# SW6208_C_LED__188.net
KiCad netlist of a schematic drawn in Altium Designer
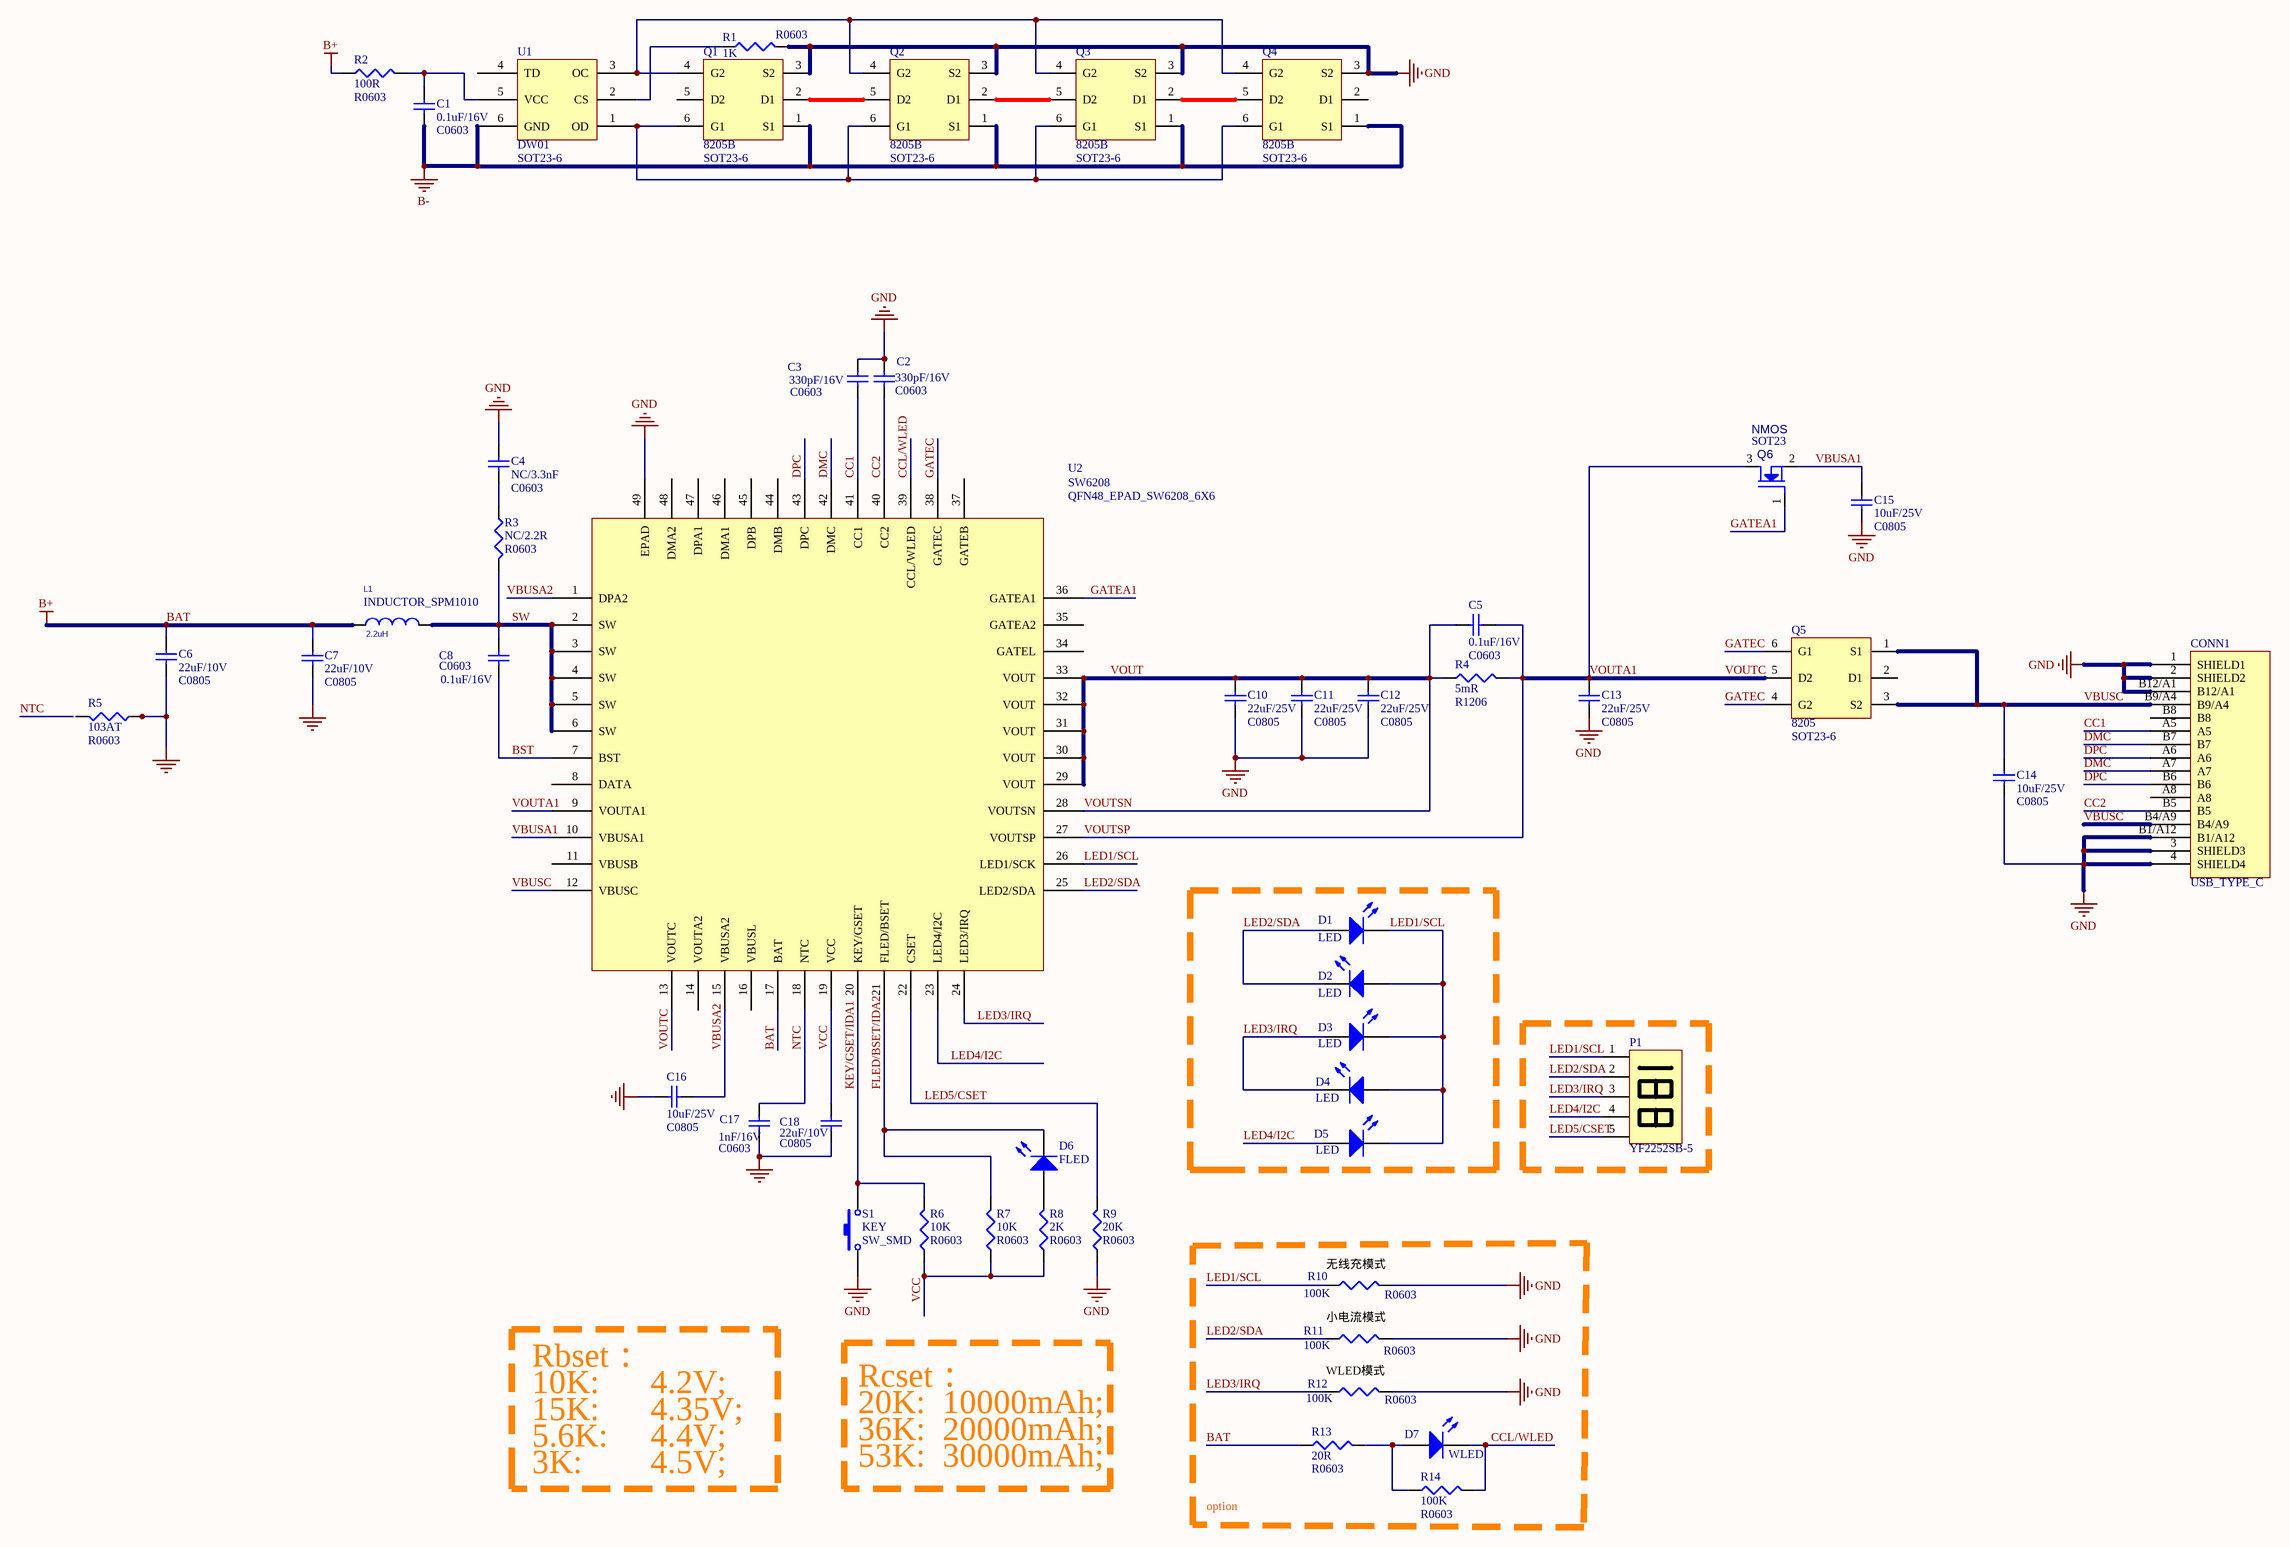
[diagram p0: SW6208+C+LED_普通188数码管.SchDoc]

(export (version "E")
  (design (tool "Eeschema 10.0.6"))
  (components
    (comp (ref "C1")
      (value "0.1uF/16V")
      (footprint "C0603")
      (description "Capacitor")
      (fields (field (name "PUBLISHER") "Altium Limited"))
      (libsource (lib "参考设计器件原理图更新") (part "CAP0603"))
    )
    (comp (ref "C2")
      (value "330pF/16V")
      (footprint "C0603")
      (description "Capacitor")
      (fields (field (name "PUBLISHER") "Altium Limited"))
      (libsource (lib "参考设计器件原理图更新") (part "CAP0603"))
    )
    (comp (ref "C3")
      (value "330pF/16V")
      (footprint "C0603")
      (description "Capacitor")
      (fields (field (name "PUBLISHER") "Altium Limited"))
      (libsource (lib "参考设计器件原理图更新") (part "CAP0603"))
    )
    (comp (ref "C4")
      (value "NC/3.3nF")
      (footprint "C0603")
      (description "Capacitor")
      (fields (field (name "PUBLISHER") "Altium Limited"))
      (libsource (lib "参考设计器件原理图更新") (part "CAP0603"))
    )
    (comp (ref "C5")
      (value "0.1uF/16V")
      (footprint "C0603")
      (description "Capacitor")
      (fields (field (name "PUBLISHER") "Altium Limited"))
      (libsource (lib "参考设计器件原理图更新") (part "CAP0603"))
    )
    (comp (ref "C6")
      (value "22uF/10V")
      (footprint "C0805")
      (description "Capacitor")
      (fields (field (name "PUBLISHER") "Altium Limited"))
      (libsource (lib "参考设计器件原理图更新") (part "CAP0805"))
    )
    (comp (ref "C7")
      (value "22uF/10V")
      (footprint "C0805")
      (description "Capacitor")
      (fields (field (name "PUBLISHER") "Altium Limited"))
      (libsource (lib "参考设计器件原理图更新") (part "CAP0805"))
    )
    (comp (ref "C8")
      (value "0.1uF/16V")
      (footprint "C0603")
      (description "Capacitor")
      (fields (field (name "PUBLISHER") "Altium Limited"))
      (libsource (lib "参考设计器件原理图更新") (part "CAP0603"))
    )
    (comp (ref "C10")
      (value "22uF/25V")
      (footprint "C0805")
      (description "Capacitor")
      (fields (field (name "PUBLISHER") "Altium Limited"))
      (libsource (lib "参考设计器件原理图更新") (part "CAP0805"))
    )
    (comp (ref "C11")
      (value "22uF/25V")
      (footprint "C0805")
      (description "Capacitor")
      (fields (field (name "PUBLISHER") "Altium Limited"))
      (libsource (lib "参考设计器件原理图更新") (part "CAP0805"))
    )
    (comp (ref "C12")
      (value "22uF/25V")
      (footprint "C0805")
      (description "Capacitor")
      (fields (field (name "PUBLISHER") "Altium Limited"))
      (libsource (lib "参考设计器件原理图更新") (part "CAP0805"))
    )
    (comp (ref "C13")
      (value "22uF/25V")
      (footprint "C0805")
      (description "Capacitor")
      (fields (field (name "PUBLISHER") "Altium Limited"))
      (libsource (lib "参考设计器件原理图更新") (part "CAP0805"))
    )
    (comp (ref "C14")
      (value "10uF/25V")
      (footprint "C0805")
      (description "Capacitor")
      (fields (field (name "PUBLISHER") "Altium Limited"))
      (libsource (lib "参考设计器件原理图更新") (part "CAP0805"))
    )
    (comp (ref "C15")
      (value "10uF/25V")
      (footprint "C0805")
      (description "Capacitor")
      (fields (field (name "PUBLISHER") "Altium Limited"))
      (libsource (lib "参考设计器件原理图更新") (part "CAP0805"))
    )
    (comp (ref "C16")
      (value "10uF/25V")
      (footprint "C0805")
      (description "Capacitor")
      (fields (field (name "PUBLISHER") "Altium Limited"))
      (libsource (lib "参考设计器件原理图更新") (part "CAP0805"))
    )
    (comp (ref "C17")
      (value "1nF/16V")
      (footprint "C0603")
      (description "Capacitor")
      (fields (field (name "PUBLISHER") "Altium Limited"))
      (libsource (lib "参考设计器件原理图更新") (part "CAP0603"))
    )
    (comp (ref "C18")
      (value "22uF/10V")
      (footprint "C0805")
      (description "Capacitor")
      (fields (field (name "PUBLISHER") "Altium Limited"))
      (libsource (lib "参考设计器件原理图更新") (part "CAP0805"))
    )
    (comp (ref "CONN1")
      (value "USB_TYPE_C")
      (footprint "LOUISAD:USB_TYPE_C")
      (libsource (lib "参考设计器件原理图更新") (part "USB_TYPE_C"))
    )
    (comp (ref "D1")
      (value "LED")
      (footprint "LED0603")
      (fields (field (name "PUBLISHER") "Altium Limited"))
      (libsource (lib "参考设计器件原理图更新") (part "LED_0603"))
    )
    (comp (ref "D2")
      (value "LED")
      (footprint "LED0603")
      (fields (field (name "PUBLISHER") "Altium Limited"))
      (libsource (lib "参考设计器件原理图更新") (part "LED_0603"))
    )
    (comp (ref "D3")
      (value "LED")
      (footprint "LED0603")
      (fields (field (name "PUBLISHER") "Altium Limited"))
      (libsource (lib "参考设计器件原理图更新") (part "LED_0603"))
    )
    (comp (ref "D4")
      (value "LED")
      (footprint "LED0603")
      (fields (field (name "PUBLISHER") "Altium Limited"))
      (libsource (lib "参考设计器件原理图更新") (part "LED_0603"))
    )
    (comp (ref "D5")
      (value "LED")
      (footprint "LED0603")
      (fields (field (name "PUBLISHER") "Altium Limited"))
      (libsource (lib "参考设计器件原理图更新") (part "LED_0603"))
    )
    (comp (ref "D6")
      (value "FLED")
      (footprint "LED0603")
      (description "LED")
      (fields (field (name "PUBLISHER") "Altium Limited"))
      (libsource (lib "参考设计器件原理图更新") (part "LED_0603"))
    )
    (comp (ref "D7")
      (value "WLED")
      (footprint "LED_5MM")
      (fields (field (name "PUBLISHER") "Altium Limited"))
      (libsource (lib "参考设计器件原理图更新") (part "WLED"))
    )
    (comp (ref "L1")
      (value "2.2uH")
      (footprint "INDUCTOR_SPM1010")
      (description "INDUCTOR")
      (libsource (lib "参考设计器件原理图更新") (part "INDUCTOR_SPM1010"))
    )
    (comp (ref "P1")
      (value "YF2252SB-5")
      (footprint "LED_Display_5")
      (description "188_LED_Display")
      (libsource (lib "参考设计器件原理图更新") (part "LED_Display_5"))
    )
    (comp (ref "Q1")
      (value "8205B")
      (footprint "SOT23-6")
      (description "NMOS")
      (fields (field (name "FOOTPRINF") "SOT23-6"))
      (libsource (lib "") (part "8205_1"))
    )
    (comp (ref "Q2")
      (value "8205B")
      (footprint "SOT23-6")
      (description "NMOS")
      (fields (field (name "FOOTPRINF") "SOT23-6"))
      (libsource (lib "") (part "8205_1"))
    )
    (comp (ref "Q3")
      (value "8205B")
      (footprint "SOT23-6")
      (description "NMOS")
      (fields (field (name "FOOTPRINF") "SOT23-6"))
      (libsource (lib "") (part "8205_1"))
    )
    (comp (ref "Q4")
      (value "8205B")
      (footprint "SOT23-6")
      (description "NMOS")
      (fields (field (name "FOOTPRINF") "SOT23-6"))
      (libsource (lib "") (part "8205_1"))
    )
    (comp (ref "Q5")
      (value "8205")
      (footprint "SOT23-6")
      (description "NMOS")
      (libsource (lib "参考设计器件原理图更新") (part "8205"))
    )
    (comp (ref "Q6") (value "NMOS") (footprint "SOT23") (libsource (lib "参考设计器件原理图更新") (part "MOSFET_N")))
    (comp (ref "R1")
      (value "1K")
      (footprint "R0603")
      (description "Resistor")
      (fields (field (name "PUBLISHER") "Altium Limited"))
      (libsource (lib "参考设计器件原理图更新") (part "RES_0603"))
    )
    (comp (ref "R2")
      (value "100R")
      (footprint "R0603")
      (description "Resistor")
      (fields (field (name "PUBLISHER") "Altium Limited"))
      (libsource (lib "参考设计器件原理图更新") (part "RES_0603"))
    )
    (comp (ref "R3")
      (value "NC/2.2R")
      (footprint "R0603")
      (description "Resistor")
      (fields (field (name "PUBLISHER") "Altium Limited"))
      (libsource (lib "参考设计器件原理图更新") (part "RES_0603"))
    )
    (comp (ref "R4")
      (value "5mR")
      (footprint "R1206")
      (description "Resistor")
      (fields (field (name "PUBLISHER") "Altium Limited"))
      (libsource (lib "参考设计器件原理图更新") (part "RES_1206"))
    )
    (comp (ref "R5")
      (value "103AT")
      (footprint "R0603")
      (description "Resistor")
      (fields (field (name "PUBLISHER") "Altium Limited"))
      (libsource (lib "参考设计器件原理图更新") (part "RES_0603"))
    )
    (comp (ref "R6")
      (value "10K")
      (footprint "R0603")
      (description "Resistor")
      (fields (field (name "PUBLISHER") "Altium Limited"))
      (libsource (lib "参考设计器件原理图更新") (part "RES_0603"))
    )
    (comp (ref "R7")
      (value "10K")
      (footprint "R0603")
      (description "Resistor")
      (fields (field (name "PUBLISHER") "Altium Limited"))
      (libsource (lib "参考设计器件原理图更新") (part "RES_0603"))
    )
    (comp (ref "R8")
      (value "2K")
      (footprint "R0603")
      (description "Resistor")
      (fields (field (name "PUBLISHER") "Altium Limited"))
      (libsource (lib "参考设计器件原理图更新") (part "RES_0603"))
    )
    (comp (ref "R9")
      (value "20K")
      (footprint "R0603")
      (description "Resistor")
      (fields (field (name "PUBLISHER") "Altium Limited"))
      (libsource (lib "参考设计器件原理图更新") (part "RES_0603"))
    )
    (comp (ref "R10")
      (value "100K")
      (footprint "R0603")
      (description "Resistor")
      (fields (field (name "PUBLISHER") "Altium Limited"))
      (libsource (lib "参考设计器件原理图更新") (part "RES_0603"))
    )
    (comp (ref "R11")
      (value "100K")
      (footprint "R0603")
      (description "Resistor")
      (fields (field (name "PUBLISHER") "Altium Limited"))
      (libsource (lib "参考设计器件原理图更新") (part "RES_0603"))
    )
    (comp (ref "R12")
      (value "100K")
      (footprint "R0603")
      (description "Resistor")
      (fields (field (name "PUBLISHER") "Altium Limited"))
      (libsource (lib "参考设计器件原理图更新") (part "RES_0603"))
    )
    (comp (ref "R13")
      (value "20R")
      (footprint "R0603")
      (description "Resistor")
      (fields (field (name "PUBLISHER") "Altium Limited"))
      (libsource (lib "参考设计器件原理图更新") (part "RES_0603"))
    )
    (comp (ref "R14")
      (value "100K")
      (footprint "R0603")
      (description "Resistor")
      (fields (field (name "PUBLISHER") "Altium Limited"))
      (libsource (lib "参考设计器件原理图更新") (part "RES_0603"))
    )
    (comp (ref "S1")
      (value "KEY")
      (footprint "SW_SMD")
      (fields (field (name "FOOTPRINF") "SW_SMD"))
      (libsource (lib "参考设计器件原理图更新") (part "SW K"))
    )
    (comp (ref "U1")
      (value "DW01")
      (footprint "SOT23-6")
      (description "BAT_PROTECT_IC")
      (libsource (lib "参考设计器件原理图更新") (part "DW01"))
    )
    (comp (ref "U2")
      (value "SW6208")
      (footprint "QFN48_EPAD_SW6208_6X6")
      (description "IC")
      (libsource (lib "芯片型号原理图") (part "SW6208"))
    )
  )
  (nets
    (net (code "1") (name "/BST") (class "Default")
      (node (ref "C8") (pin "1") (pinfunction "1_1") (pintype "passive"))
      (node (ref "U2") (pin "7") (pinfunction "BST_7") (pintype "passive"))
    )
    (net (code "2") (name "/CC1") (class "Default")
      (node (ref "C3") (pin "1") (pinfunction "1_1") (pintype "passive"))
      (node (ref "CONN1") (pin "A5") (pinfunction "A5_A5") (pintype "passive"))
      (node (ref "U2") (pin "41") (pinfunction "CC1_41") (pintype "passive"))
    )
    (net (code "3") (name "/CC2") (class "Default")
      (node (ref "C2") (pin "1") (pinfunction "1_1") (pintype "passive"))
      (node (ref "CONN1") (pin "B5") (pinfunction "B5_B5") (pintype "passive"))
      (node (ref "U2") (pin "40") (pinfunction "CC2_40") (pintype "passive"))
    )
    (net (code "4") (name "/CCL{slash}WLED") (class "Default")
      (node (ref "D7") (pin "2") (pinfunction "K_2") (pintype "passive"))
      (node (ref "R14") (pin "2") (pinfunction "2_2") (pintype "passive"))
      (node (ref "U2") (pin "39") (pinfunction "CCL/WLED_39") (pintype "passive"))
    )
    (net (code "5") (name "/DMC") (class "Default")
      (node (ref "CONN1") (pin "A7") (pinfunction "A7_A7") (pintype "passive"))
      (node (ref "CONN1") (pin "B7") (pinfunction "B7_B7") (pintype "passive"))
      (node (ref "U2") (pin "42") (pinfunction "DMC_42") (pintype "passive"))
    )
    (net (code "6") (name "/DPC") (class "Default")
      (node (ref "CONN1") (pin "A6") (pinfunction "A6_A6") (pintype "passive"))
      (node (ref "CONN1") (pin "B6") (pinfunction "B6_B6") (pintype "passive"))
      (node (ref "U2") (pin "43") (pinfunction "DPC_43") (pintype "passive"))
    )
    (net (code "7") (name "/FLED{slash}BSET{slash}IDA2") (class "Default")
      (node (ref "D6") (pin "2") (pinfunction "K_2") (pintype "passive"))
      (node (ref "R7") (pin "2") (pinfunction "2_2") (pintype "passive"))
      (node (ref "U2") (pin "21") (pinfunction "FLED/BSET_21") (pintype "passive"))
    )
    (net (code "8") (name "/GATEA1") (class "Default")
      (node (ref "Q6") (pin "1") (pinfunction "GATE_1") (pintype "passive"))
      (node (ref "U2") (pin "36") (pinfunction "GATEA1_36") (pintype "passive"))
    )
    (net (code "9") (name "/GATEC") (class "Default")
      (node (ref "Q5") (pin "4") (pinfunction "G2_4") (pintype "passive"))
      (node (ref "Q5") (pin "6") (pinfunction "G1_6") (pintype "passive"))
      (node (ref "U2") (pin "38") (pinfunction "GATEC_38") (pintype "passive"))
    )
    (net (code "10") (name "/KEY{slash}GSET{slash}IDA1") (class "Default")
      (node (ref "R6") (pin "2") (pinfunction "2_2") (pintype "passive"))
      (node (ref "S1") (pin "2") (pinfunction "2_2") (pintype "passive"))
      (node (ref "U2") (pin "20") (pinfunction "KEY/GSET_20") (pintype "passive"))
    )
    (net (code "11") (name "/LED1{slash}SCL") (class "Default")
      (node (ref "D1") (pin "2") (pinfunction "K_2") (pintype "passive"))
      (node (ref "D2") (pin "1") (pinfunction "A_1") (pintype "passive"))
      (node (ref "D3") (pin "2") (pinfunction "K_2") (pintype "passive"))
      (node (ref "D4") (pin "1") (pinfunction "A_1") (pintype "passive"))
      (node (ref "D5") (pin "2") (pinfunction "K_2") (pintype "passive"))
      (node (ref "P1") (pin "1") (pinfunction "F_1") (pintype "passive"))
      (node (ref "R10") (pin "1") (pinfunction "1_1") (pintype "passive"))
      (node (ref "U2") (pin "26") (pinfunction "LED1/SCK_26") (pintype "passive"))
    )
    (net (code "12") (name "/LED2{slash}SDA") (class "Default")
      (node (ref "D1") (pin "1") (pinfunction "A_1") (pintype "passive"))
      (node (ref "D2") (pin "2") (pinfunction "K_2") (pintype "passive"))
      (node (ref "P1") (pin "2") (pinfunction "C_2") (pintype "passive"))
      (node (ref "R11") (pin "1") (pinfunction "1_1") (pintype "passive"))
      (node (ref "U2") (pin "25") (pinfunction "LED2/SDA_25") (pintype "passive"))
    )
    (net (code "13") (name "/LED3{slash}IRQ") (class "Default")
      (node (ref "D3") (pin "1") (pinfunction "A_1") (pintype "passive"))
      (node (ref "D4") (pin "2") (pinfunction "K_2") (pintype "passive"))
      (node (ref "P1") (pin "3") (pinfunction "D_3") (pintype "passive"))
      (node (ref "R12") (pin "1") (pinfunction "1_1") (pintype "passive"))
      (node (ref "U2") (pin "24") (pinfunction "LED3/IRQ_24") (pintype "passive"))
    )
    (net (code "14") (name "/LED4{slash}I2C") (class "Default")
      (node (ref "D5") (pin "1") (pinfunction "A_1") (pintype "passive"))
      (node (ref "P1") (pin "4") (pinfunction "E_4") (pintype "passive"))
      (node (ref "U2") (pin "23") (pinfunction "LED4/I2C_23") (pintype "passive"))
    )
    (net (code "15") (name "/LED5{slash}CSET") (class "Default")
      (node (ref "P1") (pin "5") (pinfunction "G_5") (pintype "passive"))
      (node (ref "R9") (pin "2") (pinfunction "2_2") (pintype "passive"))
      (node (ref "U2") (pin "22") (pinfunction "CSET_22") (pintype "passive"))
    )
    (net (code "16") (name "/NTC") (class "Default")
      (node (ref "C17") (pin "1") (pinfunction "1_1") (pintype "passive"))
      (node (ref "U2") (pin "18") (pinfunction "NTC_18") (pintype "passive"))
    )
    (net (code "17") (name "/SW") (class "Default")
      (node (ref "C8") (pin "2") (pinfunction "2_2") (pintype "passive"))
      (node (ref "L1") (pin "2") (pinfunction "2_2") (pintype "passive"))
      (node (ref "R3") (pin "2") (pinfunction "2_2") (pintype "passive"))
      (node (ref "U2") (pin "2") (pinfunction "SW_2") (pintype "passive"))
      (node (ref "U2") (pin "3") (pinfunction "SW_3") (pintype "passive"))
      (node (ref "U2") (pin "4") (pinfunction "SW_4") (pintype "passive"))
      (node (ref "U2") (pin "5") (pinfunction "SW_5") (pintype "passive"))
      (node (ref "U2") (pin "6") (pinfunction "SW_6") (pintype "passive"))
    )
    (net (code "18") (name "/VBUSA1") (class "Default")
      (node (ref "C15") (pin "2") (pinfunction "2_2") (pintype "passive"))
      (node (ref "Q6") (pin "2") (pinfunction "SOURCE_2") (pintype "passive"))
      (node (ref "U2") (pin "10") (pinfunction "VBUSA1_10") (pintype "passive"))
    )
    (net (code "19") (name "/VBUSA2") (class "Default")
      (node (ref "C16") (pin "2") (pinfunction "2_2") (pintype "passive"))
      (node (ref "U2") (pin "1") (pinfunction "DPA2_1") (pintype "passive"))
      (node (ref "U2") (pin "15") (pinfunction "VBUSA2_15") (pintype "passive"))
    )
    (net (code "20") (name "/VBUSC") (class "Default")
      (node (ref "C14") (pin "2") (pinfunction "2_2") (pintype "passive"))
      (node (ref "CONN1") (pin "B4/A9") (pinfunction "B4/A9_B4/A9") (pintype "passive"))
      (node (ref "CONN1") (pin "B9/A4") (pinfunction "B9/A4_B9/A4") (pintype "passive"))
      (node (ref "Q5") (pin "1") (pinfunction "S1_1") (pintype "passive"))
      (node (ref "Q5") (pin "3") (pinfunction "S2_3") (pintype "passive"))
      (node (ref "U2") (pin "12") (pinfunction "VBUSC_12") (pintype "passive"))
    )
    (net (code "21") (name "/VCC") (class "Default")
      (node (ref "C18") (pin "1") (pinfunction "1_1") (pintype "passive"))
      (node (ref "R6") (pin "1") (pinfunction "1_1") (pintype "passive"))
      (node (ref "R7") (pin "1") (pinfunction "1_1") (pintype "passive"))
      (node (ref "R8") (pin "1") (pinfunction "1_1") (pintype "passive"))
      (node (ref "U2") (pin "19") (pinfunction "VCC_19") (pintype "passive"))
    )
    (net (code "22") (name "/VOUT") (class "Default")
      (node (ref "C10") (pin "2") (pinfunction "2_2") (pintype "passive"))
      (node (ref "C11") (pin "2") (pinfunction "2_2") (pintype "passive"))
      (node (ref "C12") (pin "2") (pinfunction "2_2") (pintype "passive"))
      (node (ref "C5") (pin "1") (pinfunction "1_1") (pintype "passive"))
      (node (ref "R4") (pin "1") (pinfunction "1_1") (pintype "passive"))
      (node (ref "U2") (pin "28") (pinfunction "VOUTSN_28") (pintype "passive"))
      (node (ref "U2") (pin "29") (pinfunction "VOUT_29") (pintype "passive"))
      (node (ref "U2") (pin "30") (pinfunction "VOUT_30") (pintype "passive"))
      (node (ref "U2") (pin "31") (pinfunction "VOUT_31") (pintype "passive"))
      (node (ref "U2") (pin "32") (pinfunction "VOUT_32") (pintype "passive"))
      (node (ref "U2") (pin "33") (pinfunction "VOUT_33") (pintype "passive"))
    )
    (net (code "23") (name "/VOUTA1") (class "Default")
      (node (ref "C13") (pin "2") (pinfunction "2_2") (pintype "passive"))
      (node (ref "C5") (pin "2") (pinfunction "2_2") (pintype "passive"))
      (node (ref "Q5") (pin "5") (pinfunction "D2_5") (pintype "passive"))
      (node (ref "Q6") (pin "3") (pinfunction "DRAIN_3") (pintype "passive"))
      (node (ref "R4") (pin "2") (pinfunction "2_2") (pintype "passive"))
      (node (ref "U2") (pin "13") (pinfunction "VOUTC_13") (pintype "passive"))
      (node (ref "U2") (pin "27") (pinfunction "VOUTSP_27") (pintype "passive"))
      (node (ref "U2") (pin "9") (pinfunction "VOUTA1_9") (pintype "passive"))
    )
    (net (code "24") (name "B+") (class "Default")
      (node (ref "C6") (pin "2") (pinfunction "2_2") (pintype "passive"))
      (node (ref "C7") (pin "2") (pinfunction "2_2") (pintype "passive"))
      (node (ref "L1") (pin "1") (pinfunction "1_1") (pintype "passive"))
      (node (ref "R13") (pin "1") (pinfunction "1_1") (pintype "passive"))
      (node (ref "R2") (pin "1") (pinfunction "1_1") (pintype "passive"))
      (node (ref "U2") (pin "17") (pinfunction "BAT_17") (pintype "passive"))
    )
    (net (code "25") (name "B-") (class "Default")
      (node (ref "C1") (pin "1") (pinfunction "1_1") (pintype "passive"))
      (node (ref "Q1") (pin "1") (pinfunction "S1_1") (pintype "passive"))
      (node (ref "Q2") (pin "1") (pinfunction "S1_1") (pintype "passive"))
      (node (ref "Q3") (pin "1") (pinfunction "S1_1") (pintype "passive"))
      (node (ref "Q4") (pin "1") (pinfunction "S1_1") (pintype "passive"))
      (node (ref "U1") (pin "6") (pinfunction "GND_6") (pintype "passive"))
    )
    (net (code "26") (name "GND") (class "Default")
      (node (ref "C10") (pin "1") (pinfunction "1_1") (pintype "passive"))
      (node (ref "C11") (pin "1") (pinfunction "1_1") (pintype "passive"))
      (node (ref "C12") (pin "1") (pinfunction "1_1") (pintype "passive"))
      (node (ref "C13") (pin "1") (pinfunction "1_1") (pintype "passive"))
      (node (ref "C14") (pin "1") (pinfunction "1_1") (pintype "passive"))
      (node (ref "C15") (pin "1") (pinfunction "1_1") (pintype "passive"))
      (node (ref "C16") (pin "1") (pinfunction "1_1") (pintype "passive"))
      (node (ref "C17") (pin "2") (pinfunction "2_2") (pintype "passive"))
      (node (ref "C18") (pin "2") (pinfunction "2_2") (pintype "passive"))
      (node (ref "C2") (pin "2") (pinfunction "2_2") (pintype "passive"))
      (node (ref "C3") (pin "2") (pinfunction "2_2") (pintype "passive"))
      (node (ref "C4") (pin "2") (pinfunction "2_2") (pintype "passive"))
      (node (ref "C6") (pin "1") (pinfunction "1_1") (pintype "passive"))
      (node (ref "C7") (pin "1") (pinfunction "1_1") (pintype "passive"))
      (node (ref "CONN1") (pin "1") (pinfunction "SHIELD1_1") (pintype "passive"))
      (node (ref "CONN1") (pin "2") (pinfunction "SHIELD2_2") (pintype "passive"))
      (node (ref "CONN1") (pin "3") (pinfunction "SHIELD3_3") (pintype "passive"))
      (node (ref "CONN1") (pin "4") (pinfunction "SHIELD4_4") (pintype "passive"))
      (node (ref "CONN1") (pin "B1/A12") (pinfunction "B1/A12_B1/A12") (pintype "passive"))
      (node (ref "CONN1") (pin "B12/A1") (pinfunction "B12/A1_B12/A1") (pintype "passive"))
      (node (ref "Q1") (pin "3") (pinfunction "S2_3") (pintype "passive"))
      (node (ref "Q2") (pin "3") (pinfunction "S2_3") (pintype "passive"))
      (node (ref "Q3") (pin "3") (pinfunction "S2_3") (pintype "passive"))
      (node (ref "Q4") (pin "3") (pinfunction "S2_3") (pintype "passive"))
      (node (ref "R1") (pin "2") (pinfunction "2_2") (pintype "passive"))
      (node (ref "R10") (pin "2") (pinfunction "2_2") (pintype "passive"))
      (node (ref "R11") (pin "2") (pinfunction "2_2") (pintype "passive"))
      (node (ref "R12") (pin "2") (pinfunction "2_2") (pintype "passive"))
      (node (ref "R5") (pin "1") (pinfunction "1_1") (pintype "passive"))
      (node (ref "R9") (pin "1") (pinfunction "1_1") (pintype "passive"))
      (node (ref "S1") (pin "1") (pinfunction "1_1") (pintype "passive"))
      (node (ref "U2") (pin "49") (pinfunction "EPAD_49") (pintype "passive"))
    )
    (net (code "27") (name "Net-(C4-Pad1)") (class "Default")
      (node (ref "C4") (pin "1") (pinfunction "1_1") (pintype "passive"))
      (node (ref "R3") (pin "1") (pinfunction "1_1") (pintype "passive"))
    )
    (net (code "28") (name "Net-(D6-A)") (class "Default")
      (node (ref "D6") (pin "1") (pinfunction "A_1") (pintype "passive"))
      (node (ref "R8") (pin "2") (pinfunction "2_2") (pintype "passive"))
    )
    (net (code "29") (name "Net-(D7-A)") (class "Default")
      (node (ref "D7") (pin "1") (pinfunction "A_1") (pintype "passive"))
      (node (ref "R13") (pin "2") (pinfunction "2_2") (pintype "passive"))
      (node (ref "R14") (pin "1") (pinfunction "1_1") (pintype "passive"))
    )
    (net (code "30") (name "Net-(Q1-D1)") (class "Default")
      (node (ref "Q1") (pin "2") (pinfunction "D1_2") (pintype "passive"))
      (node (ref "Q2") (pin "5") (pinfunction "D2_5") (pintype "passive"))
    )
    (net (code "31") (name "Net-(Q1-G1)") (class "Default")
      (node (ref "Q1") (pin "6") (pinfunction "G1_6") (pintype "passive"))
      (node (ref "Q2") (pin "6") (pinfunction "G1_6") (pintype "passive"))
      (node (ref "Q3") (pin "6") (pinfunction "G1_6") (pintype "passive"))
      (node (ref "Q4") (pin "6") (pinfunction "G1_6") (pintype "passive"))
      (node (ref "U1") (pin "1") (pinfunction "OD_1") (pintype "passive"))
    )
    (net (code "32") (name "Net-(Q1-G2)") (class "Default")
      (node (ref "Q1") (pin "4") (pinfunction "G2_4") (pintype "passive"))
      (node (ref "Q2") (pin "4") (pinfunction "G2_4") (pintype "passive"))
      (node (ref "Q3") (pin "4") (pinfunction "G2_4") (pintype "passive"))
      (node (ref "Q4") (pin "4") (pinfunction "G2_4") (pintype "passive"))
      (node (ref "U1") (pin "3") (pinfunction "OC_3") (pintype "passive"))
    )
    (net (code "33") (name "Net-(Q2-D1)") (class "Default")
      (node (ref "Q2") (pin "2") (pinfunction "D1_2") (pintype "passive"))
      (node (ref "Q3") (pin "5") (pinfunction "D2_5") (pintype "passive"))
    )
    (net (code "34") (name "Net-(Q3-D1)") (class "Default")
      (node (ref "Q3") (pin "2") (pinfunction "D1_2") (pintype "passive"))
      (node (ref "Q4") (pin "5") (pinfunction "D2_5") (pintype "passive"))
    )
    (net (code "35") (name "Net-(U1-CS)") (class "Default")
      (node (ref "R1") (pin "1") (pinfunction "1_1") (pintype "passive"))
      (node (ref "U1") (pin "2") (pinfunction "CS_2") (pintype "passive"))
    )
    (net (code "36") (name "Net-(U1-VCC)") (class "Default")
      (node (ref "C1") (pin "2") (pinfunction "2_2") (pintype "passive"))
      (node (ref "R2") (pin "2") (pinfunction "2_2") (pintype "passive"))
      (node (ref "U1") (pin "5") (pinfunction "VCC_5") (pintype "passive"))
    )
    (net (code "37") (name "unconnected-(CONN1-PadA8)") (class "Default")
      (node (ref "CONN1") (pin "A8") (pinfunction "A8_A8") (pintype "passive"))
    )
    (net (code "38") (name "unconnected-(CONN1-PadB8)") (class "Default")
      (node (ref "CONN1") (pin "B8") (pinfunction "B8_B8") (pintype "passive"))
    )
    (net (code "39") (name "unconnected-(Q1-D2-Pad5)") (class "Default")
      (node (ref "Q1") (pin "5") (pinfunction "D2_5") (pintype "passive"))
    )
    (net (code "40") (name "unconnected-(Q4-D1-Pad2)") (class "Default")
      (node (ref "Q4") (pin "2") (pinfunction "D1_2") (pintype "passive"))
    )
    (net (code "41") (name "unconnected-(Q5-D1-Pad2)") (class "Default")
      (node (ref "Q5") (pin "2") (pinfunction "D1_2") (pintype "passive"))
    )
    (net (code "42") (name "unconnected-(R5-Pad2)") (class "Default")
      (node (ref "R5") (pin "2") (pinfunction "2_2") (pintype "passive"))
    )
    (net (code "43") (name "unconnected-(U1-TD-Pad4)") (class "Default")
      (node (ref "U1") (pin "4") (pinfunction "TD_4") (pintype "passive"))
    )
    (net (code "44") (name "unconnected-(U2-DATA-Pad8)") (class "Default")
      (node (ref "U2") (pin "8") (pinfunction "DATA_8") (pintype "passive"))
    )
    (net (code "45") (name "unconnected-(U2-DMA1-Pad46)") (class "Default")
      (node (ref "U2") (pin "46") (pinfunction "DMA1_46") (pintype "passive"))
    )
    (net (code "46") (name "unconnected-(U2-DMA2-Pad48)") (class "Default")
      (node (ref "U2") (pin "48") (pinfunction "DMA2_48") (pintype "passive"))
    )
    (net (code "47") (name "unconnected-(U2-DMB-Pad44)") (class "Default")
      (node (ref "U2") (pin "44") (pinfunction "DMB_44") (pintype "passive"))
    )
    (net (code "48") (name "unconnected-(U2-DPA1-Pad47)") (class "Default")
      (node (ref "U2") (pin "47") (pinfunction "DPA1_47") (pintype "passive"))
    )
    (net (code "49") (name "unconnected-(U2-DPB-Pad45)") (class "Default")
      (node (ref "U2") (pin "45") (pinfunction "DPB_45") (pintype "passive"))
    )
    (net (code "50") (name "unconnected-(U2-GATEA2-Pad35)") (class "Default")
      (node (ref "U2") (pin "35") (pinfunction "GATEA2_35") (pintype "passive"))
    )
    (net (code "51") (name "unconnected-(U2-GATEB-Pad37)") (class "Default")
      (node (ref "U2") (pin "37") (pinfunction "GATEB_37") (pintype "passive"))
    )
    (net (code "52") (name "unconnected-(U2-GATEL-Pad34)") (class "Default")
      (node (ref "U2") (pin "34") (pinfunction "GATEL_34") (pintype "passive"))
    )
    (net (code "53") (name "unconnected-(U2-VBUSB-Pad11)") (class "Default")
      (node (ref "U2") (pin "11") (pinfunction "VBUSB_11") (pintype "passive"))
    )
    (net (code "54") (name "unconnected-(U2-VBUSL-Pad16)") (class "Default")
      (node (ref "U2") (pin "16") (pinfunction "VBUSL_16") (pintype "passive"))
    )
    (net (code "55") (name "unconnected-(U2-VOUTA2-Pad14)") (class "Default")
      (node (ref "U2") (pin "14") (pinfunction "VOUTA2_14") (pintype "passive"))
    )
  )
)
